# STM32F050F_Base.net
KiCad netlist of a schematic drawn in EAGLE
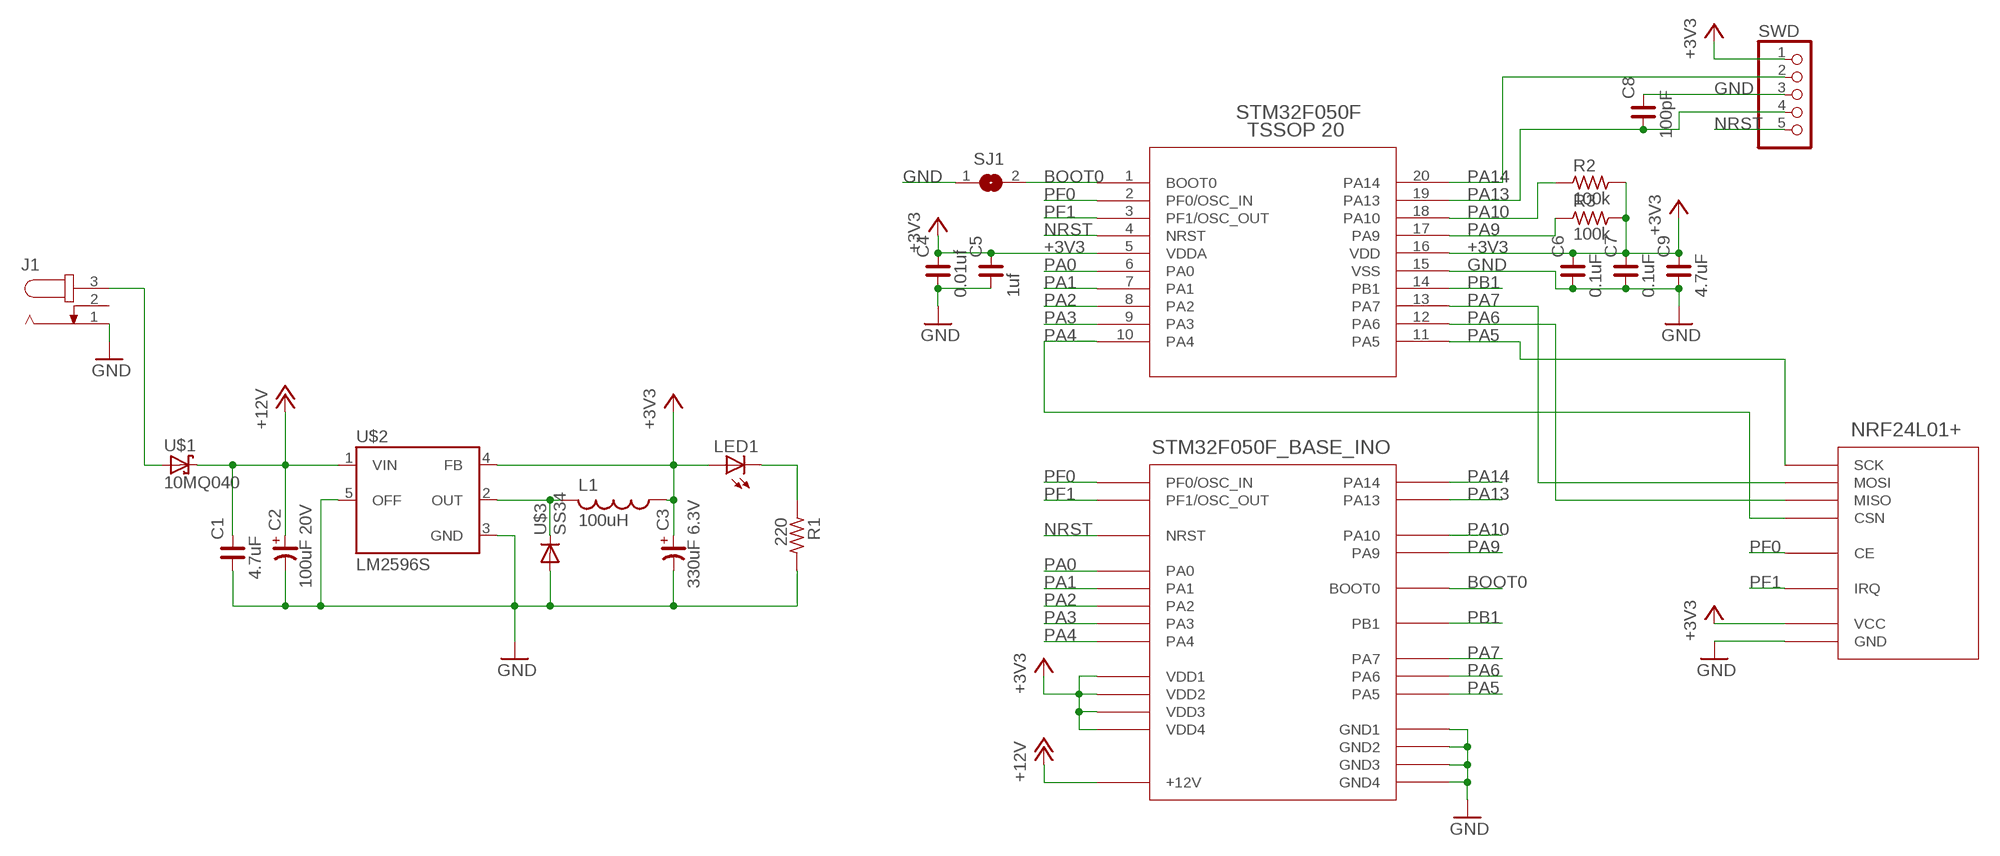
[diagram p0: schematic, sheet 1]

(export (version "E")
  (design (tool "Eeschema 10.0.6"))
  (components
    (comp (ref "C1")
      (value "4.7uF")
      (footprint "eagle-import:C1206")
      (libsource (lib "eagle-import") (part "C_1206"))
    )
    (comp (ref "C2")
      (value "100uF 20V")
      (footprint "eagle-import:C7343_T")
      (libsource (lib "eagle-import") (part "CP_7343"))
    )
    (comp (ref "C3")
      (value "330uF 6.3V")
      (footprint "eagle-import:C7343_T")
      (libsource (lib "eagle-import") (part "CP_7343"))
    )
    (comp (ref "C4")
      (value "0.01uf")
      (footprint "eagle-import:C1206")
      (libsource (lib "eagle-import") (part "C_1206"))
    )
    (comp (ref "C5")
      (value "1uf")
      (footprint "eagle-import:C1206")
      (libsource (lib "eagle-import") (part "C_1206"))
    )
    (comp (ref "C6")
      (value "0.1uF")
      (footprint "eagle-import:C1206")
      (libsource (lib "eagle-import") (part "C_1206"))
    )
    (comp (ref "C7")
      (value "0.1uF")
      (footprint "eagle-import:C1206")
      (libsource (lib "eagle-import") (part "C_1206"))
    )
    (comp (ref "C8")
      (value "100pF")
      (footprint "eagle-import:C1206")
      (libsource (lib "eagle-import") (part "C_1206"))
    )
    (comp (ref "C9")
      (value "4.7uF")
      (footprint "eagle-import:C1206")
      (libsource (lib "eagle-import") (part "C_1206"))
    )
    (comp (ref "J1")
      (value "JACK-PLUG0")
      (footprint "eagle-import:SPC4077")
      (libsource (lib "eagle-import") (part "JACK-PLUG0"))
    )
    (comp (ref "L1")
      (value "100uH")
      (footprint "eagle-import:POWER-CHOKE_WE-TPC")
      (libsource (lib "eagle-import") (part "L-USWE-TPC"))
    )
    (comp (ref "LED1")
      (value "LEDCHIPLED_1206")
      (footprint "eagle-import:CHIPLED_1206")
      (libsource (lib "eagle-import") (part "LEDCHIPLED_1206"))
    )
    (comp (ref "R1")
      (value "220")
      (footprint "eagle-import:R1206")
      (libsource (lib "eagle-import") (part "R_1206"))
    )
    (comp (ref "R2")
      (value "100k")
      (footprint "eagle-import:R1206")
      (libsource (lib "eagle-import") (part "R_1206"))
    )
    (comp (ref "R3")
      (value "100k")
      (footprint "eagle-import:R1206")
      (libsource (lib "eagle-import") (part "R_1206"))
    )
    (comp (ref "SJ1") (value "SJ") (footprint "eagle-import:SJ") (libsource (lib "eagle-import") (part "SJ")))
    (comp (ref "SWD")
      (value "PINHD-1X05_2.54-90°-S")
      (footprint "eagle-import:1X05_90-S")
      (libsource (lib "eagle-import") (part "PINHD-1X05_2.54-90°-S"))
    )
    (comp (ref "U$1")
      (value "10MQ040")
      (footprint "eagle-import:SMA")
      (libsource (lib "eagle-import") (part "10MQ040"))
    )
    (comp (ref "U$2")
      (value "LM2596S")
      (footprint "eagle-import:TO263-5")
      (libsource (lib "eagle-import") (part "LM2596S"))
    )
    (comp (ref "U$3")
      (value "SS34")
      (footprint "eagle-import:SMC")
      (libsource (lib "eagle-import") (part "DIODE-SMC"))
    )
    (comp (ref "U$4")
      (value "STM32F050F4P6")
      (footprint "eagle-import:TSSOP20")
      (libsource (lib "eagle-import") (part "STM32F050F4P6"))
    )
    (comp (ref "U$5")
      (value "STM32F050F_BASE_INO")
      (footprint "eagle-import:STM32_BASE_INO")
      (libsource (lib "eagle-import") (part "STM32F050F_BASE_INO"))
    )
    (comp (ref "U$6")
      (value "NRF24L01+")
      (footprint "eagle-import:NRF24L01+")
      (libsource (lib "eagle-import") (part "NRF24L01+"))
    )
  )
  (nets
    (net (code "1") (name "+3V3") (class "Default")
      (node (ref "C3") (pin "+") (pinfunction "+_+") (pintype "passive"))
      (node (ref "C4") (pin "2") (pinfunction "2_2") (pintype "passive"))
      (node (ref "C5") (pin "2") (pinfunction "2_2") (pintype "passive"))
      (node (ref "C6") (pin "2") (pinfunction "2_2") (pintype "passive"))
      (node (ref "C7") (pin "2") (pinfunction "2_2") (pintype "passive"))
      (node (ref "C9") (pin "2") (pinfunction "2_2") (pintype "passive"))
      (node (ref "L1") (pin "1") (pinfunction "1_1") (pintype "passive"))
      (node (ref "LED1") (pin "A") (pinfunction "A_A") (pintype "passive"))
      (node (ref "R2") (pin "2") (pinfunction "2_2") (pintype "passive"))
      (node (ref "R3") (pin "2") (pinfunction "2_2") (pintype "passive"))
      (node (ref "SWD") (pin "1") (pinfunction "1_1") (pintype "passive"))
      (node (ref "U$2") (pin "4") (pinfunction "FB_4") (pintype "input"))
      (node (ref "U$4") (pin "16") (pinfunction "VDD_16") (pintype "passive"))
      (node (ref "U$4") (pin "5") (pinfunction "VDDA_5") (pintype "passive"))
      (node (ref "U$5") (pin "VDD1") (pinfunction "VDD1_VDD1") (pintype "passive"))
      (node (ref "U$5") (pin "VDD2") (pinfunction "VDD2_VDD2") (pintype "passive"))
      (node (ref "U$5") (pin "VDD3") (pinfunction "VDD3_VDD3") (pintype "passive"))
      (node (ref "U$5") (pin "VDD4") (pinfunction "VDD4_VDD4") (pintype "passive"))
      (node (ref "U$6") (pin "VCC") (pinfunction "VCC_VCC") (pintype "passive"))
    )
    (net (code "2") (name "+12V") (class "Default")
      (node (ref "C1") (pin "2") (pinfunction "2_2") (pintype "passive"))
      (node (ref "C2") (pin "+") (pinfunction "+_+") (pintype "passive"))
      (node (ref "U$1") (pin "C") (pinfunction "C_C") (pintype "passive"))
      (node (ref "U$2") (pin "1") (pinfunction "VIN_1") (pintype "power_in"))
      (node (ref "U$5") (pin "+12V") (pinfunction "+12V_+12V") (pintype "passive"))
    )
    (net (code "3") (name "/BOOT0") (class "Default")
      (node (ref "SJ1") (pin "2") (pinfunction "2_2") (pintype "passive"))
      (node (ref "U$4") (pin "1") (pinfunction "BOOT0_1") (pintype "passive"))
      (node (ref "U$5") (pin "BOOT0") (pinfunction "BOOT0_BOOT0") (pintype "passive"))
    )
    (net (code "4") (name "/NRST") (class "Default")
      (node (ref "SWD") (pin "5") (pinfunction "5_5") (pintype "passive"))
      (node (ref "U$4") (pin "4") (pinfunction "NRST_4") (pintype "passive"))
      (node (ref "U$5") (pin "NRST") (pinfunction "NRST_NRST") (pintype "passive"))
    )
    (net (code "5") (name "/PA0") (class "Default")
      (node (ref "U$4") (pin "6") (pinfunction "PA0_6") (pintype "passive"))
      (node (ref "U$5") (pin "PA0") (pinfunction "PA0_PA0") (pintype "passive"))
    )
    (net (code "6") (name "/PA1") (class "Default")
      (node (ref "U$4") (pin "7") (pinfunction "PA1_7") (pintype "passive"))
      (node (ref "U$5") (pin "PA1") (pinfunction "PA1_PA1") (pintype "passive"))
    )
    (net (code "7") (name "/PA2") (class "Default")
      (node (ref "U$4") (pin "8") (pinfunction "PA2_8") (pintype "passive"))
      (node (ref "U$5") (pin "PA2") (pinfunction "PA2_PA2") (pintype "passive"))
    )
    (net (code "8") (name "/PA3") (class "Default")
      (node (ref "U$4") (pin "9") (pinfunction "PA3_9") (pintype "passive"))
      (node (ref "U$5") (pin "PA3") (pinfunction "PA3_PA3") (pintype "passive"))
    )
    (net (code "9") (name "/PA4") (class "Default")
      (node (ref "U$4") (pin "10") (pinfunction "PA4_10") (pintype "passive"))
      (node (ref "U$5") (pin "PA4") (pinfunction "PA4_PA4") (pintype "passive"))
      (node (ref "U$6") (pin "CSN") (pinfunction "CSN_CSN") (pintype "passive"))
    )
    (net (code "10") (name "/PA5") (class "Default")
      (node (ref "U$4") (pin "11") (pinfunction "PA5_11") (pintype "passive"))
      (node (ref "U$5") (pin "PA5") (pinfunction "PA5_PA5") (pintype "passive"))
      (node (ref "U$6") (pin "SCK") (pinfunction "SCK_SCK") (pintype "passive"))
    )
    (net (code "11") (name "/PA6") (class "Default")
      (node (ref "U$4") (pin "12") (pinfunction "PA6_12") (pintype "passive"))
      (node (ref "U$5") (pin "PA6") (pinfunction "PA6_PA6") (pintype "passive"))
      (node (ref "U$6") (pin "MISO") (pinfunction "MISO_MISO") (pintype "passive"))
    )
    (net (code "12") (name "/PA7") (class "Default")
      (node (ref "U$4") (pin "13") (pinfunction "PA7_13") (pintype "passive"))
      (node (ref "U$5") (pin "PA7") (pinfunction "PA7_PA7") (pintype "passive"))
      (node (ref "U$6") (pin "MOSI") (pinfunction "MOSI_MOSI") (pintype "passive"))
    )
    (net (code "13") (name "/PA9") (class "Default")
      (node (ref "R3") (pin "1") (pinfunction "1_1") (pintype "passive"))
      (node (ref "U$4") (pin "17") (pinfunction "PA9_17") (pintype "passive"))
      (node (ref "U$5") (pin "PA9") (pinfunction "PA9_PA9") (pintype "passive"))
    )
    (net (code "14") (name "/PA10") (class "Default")
      (node (ref "R2") (pin "1") (pinfunction "1_1") (pintype "passive"))
      (node (ref "U$4") (pin "18") (pinfunction "PA10_18") (pintype "passive"))
      (node (ref "U$5") (pin "PA10") (pinfunction "PA10_PA10") (pintype "passive"))
    )
    (net (code "15") (name "/PA13") (class "Default")
      (node (ref "C8") (pin "1") (pinfunction "1_1") (pintype "passive"))
      (node (ref "SWD") (pin "4") (pinfunction "4_4") (pintype "passive"))
      (node (ref "U$4") (pin "19") (pinfunction "PA13_19") (pintype "passive"))
      (node (ref "U$5") (pin "PA13") (pinfunction "PA13_PA13") (pintype "passive"))
    )
    (net (code "16") (name "/PA14") (class "Default")
      (node (ref "SWD") (pin "2") (pinfunction "2_2") (pintype "passive"))
      (node (ref "U$4") (pin "20") (pinfunction "PA14_20") (pintype "passive"))
      (node (ref "U$5") (pin "PA14") (pinfunction "PA14_PA14") (pintype "passive"))
    )
    (net (code "17") (name "/PB1") (class "Default")
      (node (ref "U$4") (pin "14") (pinfunction "PB1_14") (pintype "passive"))
      (node (ref "U$5") (pin "PB1") (pinfunction "PB1_PB1") (pintype "passive"))
    )
    (net (code "18") (name "/PF0") (class "Default")
      (node (ref "U$4") (pin "2") (pinfunction "PF0/OSC_IN_2") (pintype "passive"))
      (node (ref "U$5") (pin "PF0") (pinfunction "PF0/OSC_IN_PF0") (pintype "passive"))
      (node (ref "U$6") (pin "CE") (pinfunction "CE_CE") (pintype "passive"))
    )
    (net (code "19") (name "/PF1") (class "Default")
      (node (ref "U$4") (pin "3") (pinfunction "PF1/OSC_OUT_3") (pintype "passive"))
      (node (ref "U$5") (pin "PF1") (pinfunction "PF1/OSC_OUT_PF1") (pintype "passive"))
      (node (ref "U$6") (pin "IRQ") (pinfunction "IRQ_IRQ") (pintype "passive"))
    )
    (net (code "20") (name "GND") (class "Default")
      (node (ref "C1") (pin "1") (pinfunction "1_1") (pintype "passive"))
      (node (ref "C2") (pin "-") (pinfunction "-_-") (pintype "passive"))
      (node (ref "C3") (pin "-") (pinfunction "-_-") (pintype "passive"))
      (node (ref "C4") (pin "1") (pinfunction "1_1") (pintype "passive"))
      (node (ref "C5") (pin "1") (pinfunction "1_1") (pintype "passive"))
      (node (ref "C6") (pin "1") (pinfunction "1_1") (pintype "passive"))
      (node (ref "C7") (pin "1") (pinfunction "1_1") (pintype "passive"))
      (node (ref "C8") (pin "2") (pinfunction "2_2") (pintype "passive"))
      (node (ref "C9") (pin "1") (pinfunction "1_1") (pintype "passive"))
      (node (ref "J1") (pin "1") (pinfunction "1_1") (pintype "passive"))
      (node (ref "R1") (pin "2") (pinfunction "2_2") (pintype "passive"))
      (node (ref "SJ1") (pin "1") (pinfunction "1_1") (pintype "passive"))
      (node (ref "SWD") (pin "3") (pinfunction "3_3") (pintype "passive"))
      (node (ref "U$2") (pin "3") (pinfunction "GND_3") (pintype "power_in"))
      (node (ref "U$2") (pin "5") (pinfunction "OFF_5") (pintype "input"))
      (node (ref "U$3") (pin "A") (pinfunction "A_A") (pintype "passive"))
      (node (ref "U$4") (pin "15") (pinfunction "VSS_15") (pintype "passive"))
      (node (ref "U$5") (pin "GND1") (pinfunction "GND1_GND1") (pintype "passive"))
      (node (ref "U$5") (pin "GND2") (pinfunction "GND2_GND2") (pintype "passive"))
      (node (ref "U$5") (pin "GND3") (pinfunction "GND3_GND3") (pintype "passive"))
      (node (ref "U$5") (pin "GND4") (pinfunction "GND4_GND4") (pintype "passive"))
      (node (ref "U$6") (pin "GND") (pinfunction "GND_GND") (pintype "passive"))
    )
    (net (code "21") (name "Net-(J1-Pad3)") (class "Default")
      (node (ref "J1") (pin "3") (pinfunction "3_3") (pintype "passive"))
      (node (ref "U$1") (pin "A") (pinfunction "A_A") (pintype "passive"))
    )
    (net (code "22") (name "Net-(LED1-PadC)") (class "Default")
      (node (ref "LED1") (pin "C") (pinfunction "C_C") (pintype "passive"))
      (node (ref "R1") (pin "1") (pinfunction "1_1") (pintype "passive"))
    )
    (net (code "23") (name "Net-(U$2-OUT)") (class "Default")
      (node (ref "L1") (pin "2") (pinfunction "2_2") (pintype "passive"))
      (node (ref "U$2") (pin "2") (pinfunction "OUT_2") (pintype "output"))
      (node (ref "U$3") (pin "C") (pinfunction "C_C") (pintype "passive"))
    )
    (net (code "24") (name "unconnected-(J1-Pad2)") (class "Default")
      (node (ref "J1") (pin "2") (pinfunction "2_2") (pintype "passive"))
    )
  )
)
